# Converter_3V3-0V9_V2.net
KiCad netlist of a schematic drawn in Altium Designer
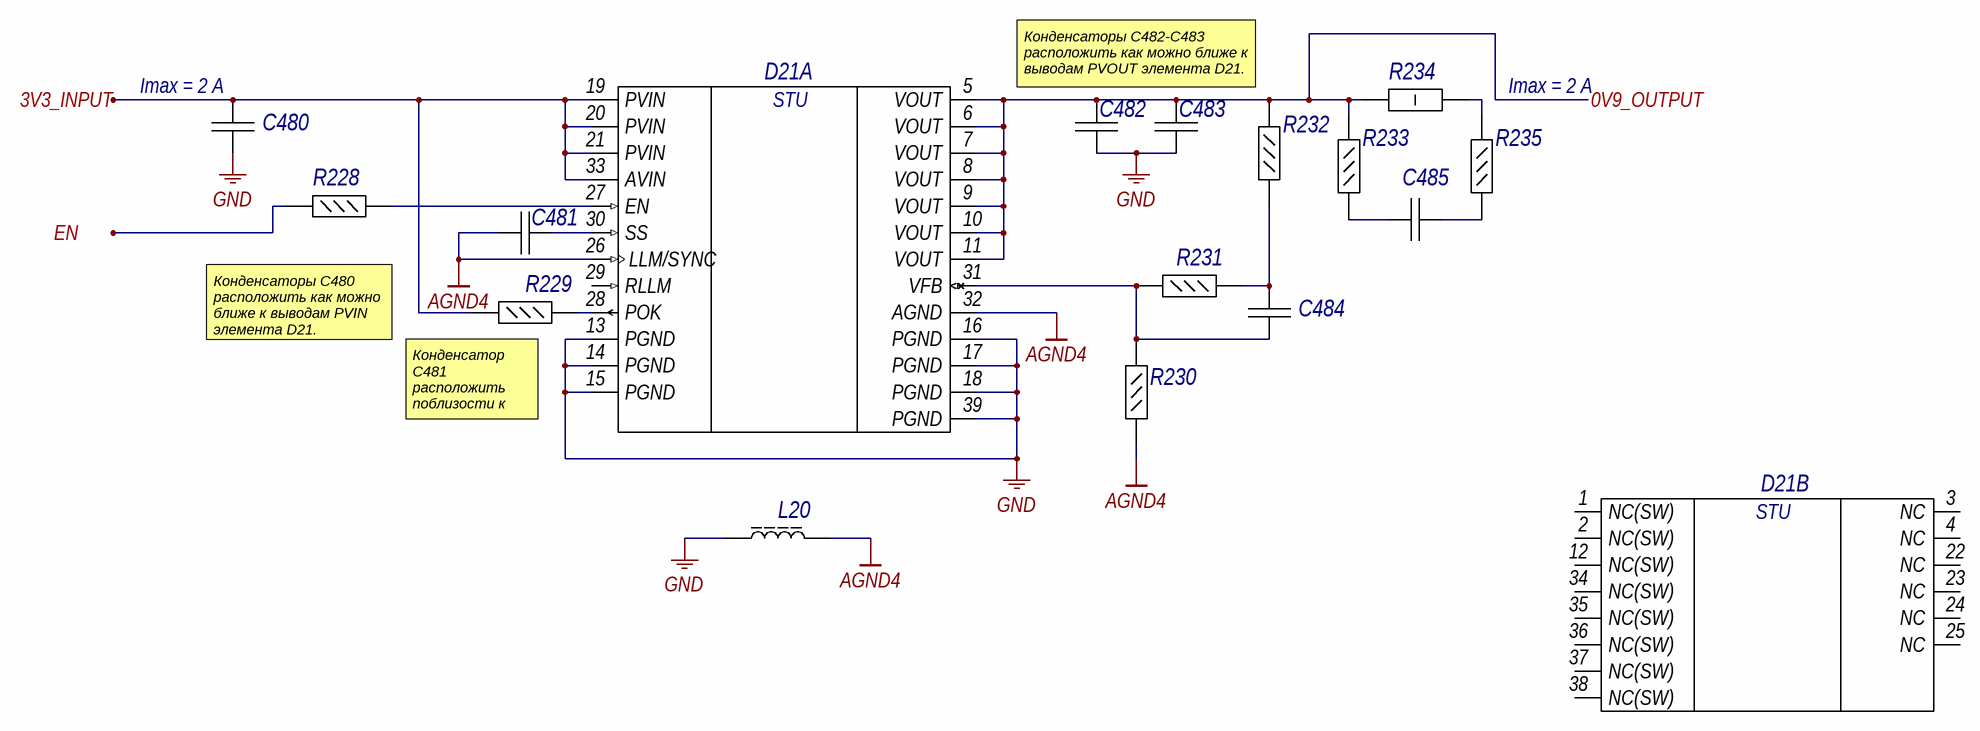
[diagram p0: Converter 3V3-0V9 V2.SchDoc]

(export (version "E")
  (design (tool "Eeschema 10.0.6"))
  (components
    (comp (ref "C480")
      (value "GRM31CR61E226KE15L")
      (footprint "CAPC3216X180X55ML20T25")
      (description "Chip Capacitor, 22 uF, +/- 10%, 25 V, -55 to 85 degC, 1206 (3216 Metric), RoHS, Tape and Reel")
      (fields (field (name "TOLERANCE") "10%"))
      (libsource (lib "MiniPC DB") (part "CAP_NP"))
    )
    (comp (ref "C481")
      (value "VJ0402Y153JXQPW1BC")
      (footprint "CAPC1005X55X23ML05T8")
      (description "Chip Capacitor, 15 nF, +/- 5%, 10 V, -55 to 125 degC, 0402 (1005 Metric), RoHS, Tape and Reel")
      (fields (field (name "TOLERANCE") "5%"))
      (libsource (lib "MiniPC DB") (part "CAP_NP"))
    )
    (comp (ref "C482")
      (value "C3216X5R1A476M160AB")
      (footprint "CAPC3216X180X20ML20")
      (description "Chip Capacitor, 47 uF, +/- 20%, 10 V, -55 to 85 degC, 1206 (3216 Metric), RoHS, Tape and Reel")
      (fields (field (name "TOLERANCE") "20%"))
      (libsource (lib "MiniPC DB") (part "CAP_NP"))
    )
    (comp (ref "C483")
      (value "C3216X5R1A476M160AB")
      (footprint "CAPC3216X180X20ML20")
      (description "Chip Capacitor, 47 uF, +/- 20%, 10 V, -55 to 85 degC, 1206 (3216 Metric), RoHS, Tape and Reel")
      (fields (field (name "TOLERANCE") "20%"))
      (libsource (lib "MiniPC DB") (part "CAP_NP"))
    )
    (comp (ref "C484")
      (value "ECJ-0EC1H150J")
      (footprint "CAPC1005X55X20ML5T10")
      (description "Chip Capacitor,15 pF, +/- 5%, 50 V, -55 to 125 degC, 0402 (1005 Metric), RoHS, Tape and Reel")
      (fields (field (name "TOLERANCE") "5%"))
      (libsource (lib "MiniPC DB") (part "CAP_NP"))
    )
    (comp (ref "C485")
      (value "CGB2A1X5R1E105K033BC")
      (footprint "CAPC1005X33X10LL5")
      (description "Chip Capacitor, 1 uF, +/- 10%, 25 V, -55 to 85 degC, 0402 (1005 Metric), RoHS, Tape and Reel")
      (fields (field (name "TOLERANCE") "10%"))
      (libsource (lib "MiniPC DB") (part "CAP_NP"))
    )
    (comp (ref "D21")
      (value "EN6337QI")
      (footprint "ALTR-QFN-38_A-190_D1-193_V")
      (libsource (lib "MiniPC DB") (part "EN6337QI"))
    )
    (comp (ref "L20")
      (value "742792609")
      (footprint "SMD-0603")
      (description "SMD EMI Suppression Ferrite Bead WE-CBF, Z = 30 Ohm")
      (libsource (lib "MiniPC DB") (part "Choke"))
    )
    (comp (ref "R228")
      (value "NRC04F49R9TRF")
      (footprint "RESC1005X35X25NL8T10")
      (description "Chip Resistor, 49.9 Ohm, +/- 1%, 0.06 W, -55 to 155 degC, 0402 (1005 Metric), RoHS, Tape and Reel")
      (fields (field (name "TOLERANCE") "1%"))
      (libsource (lib "") (part "RES-0.05_1"))
    )
    (comp (ref "R229")
      (value "ERJ-2RKF1003X")
      (footprint "RESC1005X40X25LL05T05")
      (description "Chip Resistor, 100 KOhm, +/- 1%, 100 mW, -55 to 155 degC, 0402 (1005 Metric), RoHS, Tape and Reel")
      (fields (field (name "TOLERANCE") "1%") (field (name "MANUFACTURER") "Basic Passives"))
      (libsource (lib "") (part "RES-0.05_1"))
    )
    (comp (ref "R230")
      (value "ERJ-2RKF1004X")
      (footprint "RESC1005X40X25LL05T05")
      (description "Chip Resistor, 1 MOhm, +/- 1%, 100 mW, -55 to 155 degC, 0402 (1005 Metric), RoHS, Tape and Reel")
      (fields (field (name "TOLERANCE") "1%") (field (name "MANUFACTURER") "Basic Passives"))
      (libsource (lib "") (part "RES-0.05_2"))
    )
    (comp (ref "R231")
      (value "ERJ-2RKF2003X")
      (footprint "RESC1005X40X25LL05T05")
      (description "Chip Resistor, 200 KOhm, +/- 1%, 100 mW, -55 to 155 degC, 0402 (1005 Metric), RoHS, Tape and Reel")
      (fields (field (name "TOLERANCE") "1%") (field (name "MANUFACTURER") "Basic Passives"))
      (libsource (lib "") (part "RES-0.05_1"))
    )
    (comp (ref "R232")
      (value "ERJ-2GE0R00X")
      (footprint "RESC1005X40X25LL05T05")
      (description "Chip Resistor, 0 mOhm, +/- 5%, 100 mW, -55 to 155 degC, 0402 (1005 Metric), RoHS, Tape and Reel")
      (fields (field (name "TOLERANCE") "5%") (field (name "MANUFACTURER") "Basic Passives"))
      (libsource (lib "MiniPC DB") (part "RES-0.05"))
    )
    (comp (ref "R233")
      (value "ERJ-2RKF1002X")
      (footprint "RESC1005X40X25LL05T05")
      (description "Chip Resistor, 10 KOhm, +/- 1%, 100 mW, -55 to 155 degC, 0402 (1005 Metric), RoHS, Tape and Reel")
      (fields (field (name "TOLERANCE") "1%") (field (name "MANUFACTURER") "Basic Passives"))
      (libsource (lib "") (part "RES-0.05_2"))
    )
    (comp (ref "R234")
      (value "WSLP12061L000FEA")
      (footprint "RESC3216X89X104LL25T25")
      (description "Chip Resistor, 0.001 Ohm, +/- 1%, 1 W, -65 to 170 degC, 1206 (3216 Metric), RoHS, Tape and Reel")
      (fields (field (name "TOLERANCE") "1%"))
      (libsource (lib "MiniPC DB") (part "RES-1"))
    )
    (comp (ref "R235")
      (value "ERJ-2RKF1002X")
      (footprint "RESC1005X40X25LL05T05")
      (description "Chip Resistor, 10 KOhm, +/- 1%, 100 mW, -55 to 155 degC, 0402 (1005 Metric), RoHS, Tape and Reel")
      (fields (field (name "TOLERANCE") "1%") (field (name "MANUFACTURER") "Basic Passives"))
      (libsource (lib "") (part "RES-0.05_2"))
    )
  )
  (nets
    (net (code "1") (name "/0V9_OUTPUT") (class "Default")
      (node (ref "C482") (pin "2") (pinfunction "2_2") (pintype "passive"))
      (node (ref "C483") (pin "2") (pinfunction "2_2") (pintype "passive"))
      (node (ref "D21") (pin "10") (pinfunction "VOUT_10") (pintype "power_in"))
      (node (ref "D21") (pin "11") (pinfunction "VOUT_11") (pintype "power_in"))
      (node (ref "D21") (pin "5") (pinfunction "VOUT_5") (pintype "power_in"))
      (node (ref "D21") (pin "6") (pinfunction "VOUT_6") (pintype "power_in"))
      (node (ref "D21") (pin "7") (pinfunction "VOUT_7") (pintype "power_in"))
      (node (ref "D21") (pin "8") (pinfunction "VOUT_8") (pintype "power_in"))
      (node (ref "D21") (pin "9") (pinfunction "VOUT_9") (pintype "power_in"))
      (node (ref "R232") (pin "1") (pinfunction "1_1") (pintype "passive"))
      (node (ref "R233") (pin "2") (pinfunction "2_2") (pintype "passive"))
      (node (ref "R234") (pin "2") (pinfunction "2_2") (pintype "passive"))
    )
    (net (code "2") (name "/3V3_INPUT") (class "Default")
      (node (ref "C480") (pin "2") (pinfunction "2_2") (pintype "passive"))
      (node (ref "D21") (pin "19") (pinfunction "PVIN_19") (pintype "power_in"))
      (node (ref "D21") (pin "20") (pinfunction "PVIN_20") (pintype "power_in"))
      (node (ref "D21") (pin "21") (pinfunction "PVIN_21") (pintype "power_in"))
      (node (ref "D21") (pin "33") (pinfunction "AVIN_33") (pintype "power_in"))
      (node (ref "R229") (pin "1") (pinfunction "1_1") (pintype "passive"))
    )
    (net (code "3") (name "/EN") (class "Default")
      (node (ref "R228") (pin "1") (pinfunction "1_1") (pintype "passive"))
    )
    (net (code "4") (name "AGND4") (class "Default")
      (node (ref "C481") (pin "1") (pinfunction "1_1") (pintype "passive"))
      (node (ref "D21") (pin "26") (pinfunction "LLM/SYNC_26") (pintype "input"))
      (node (ref "D21") (pin "32") (pinfunction "AGND_32") (pintype "power_in"))
      (node (ref "L20") (pin "2") (pinfunction "2_2") (pintype "passive"))
      (node (ref "R230") (pin "1") (pinfunction "1_1") (pintype "passive"))
    )
    (net (code "5") (name "GND") (class "Default")
      (node (ref "C480") (pin "1") (pinfunction "1_1") (pintype "passive"))
      (node (ref "C482") (pin "1") (pinfunction "1_1") (pintype "passive"))
      (node (ref "C483") (pin "1") (pinfunction "1_1") (pintype "passive"))
      (node (ref "D21") (pin "13") (pinfunction "PGND_13") (pintype "power_in"))
      (node (ref "D21") (pin "14") (pinfunction "PGND_14") (pintype "power_in"))
      (node (ref "D21") (pin "15") (pinfunction "PGND_15") (pintype "power_in"))
      (node (ref "D21") (pin "16") (pinfunction "PGND_16") (pintype "power_in"))
      (node (ref "D21") (pin "17") (pinfunction "PGND_17") (pintype "power_in"))
      (node (ref "D21") (pin "18") (pinfunction "PGND_18") (pintype "power_in"))
      (node (ref "D21") (pin "39") (pinfunction "PGND_39") (pintype "power_in"))
      (node (ref "L20") (pin "1") (pinfunction "1_1") (pintype "passive"))
    )
    (net (code "6") (name "Net-(C484-Pad2)") (class "Default")
      (node (ref "C484") (pin "2") (pinfunction "2_2") (pintype "passive"))
      (node (ref "R231") (pin "2") (pinfunction "2_2") (pintype "passive"))
      (node (ref "R232") (pin "2") (pinfunction "2_2") (pintype "passive"))
    )
    (net (code "7") (name "Net-(C485-Pad1)") (class "Default")
      (node (ref "C485") (pin "1") (pinfunction "1_1") (pintype "passive"))
      (node (ref "R233") (pin "1") (pinfunction "1_1") (pintype "passive"))
    )
    (net (code "8") (name "Net-(C485-Pad2)") (class "Default")
      (node (ref "C485") (pin "2") (pinfunction "2_2") (pintype "passive"))
      (node (ref "R235") (pin "1") (pinfunction "1_1") (pintype "passive"))
    )
    (net (code "9") (name "Net-(D21A-EN)") (class "Default")
      (node (ref "D21") (pin "27") (pinfunction "EN_27") (pintype "input"))
      (node (ref "R228") (pin "2") (pinfunction "2_2") (pintype "passive"))
    )
    (net (code "10") (name "Net-(D21A-POK)") (class "Default")
      (node (ref "D21") (pin "28") (pinfunction "POK_28") (pintype "open_collector"))
      (node (ref "R229") (pin "2") (pinfunction "2_2") (pintype "passive"))
    )
    (net (code "11") (name "Net-(D21A-SS)") (class "Default")
      (node (ref "C481") (pin "2") (pinfunction "2_2") (pintype "passive"))
      (node (ref "D21") (pin "30") (pinfunction "SS_30") (pintype "input"))
    )
    (net (code "12") (name "Net-(D21A-VFB)") (class "Default")
      (node (ref "C484") (pin "1") (pinfunction "1_1") (pintype "passive"))
      (node (ref "D21") (pin "31") (pinfunction "VFB_31") (pintype "input"))
      (node (ref "R230") (pin "2") (pinfunction "2_2") (pintype "passive"))
      (node (ref "R231") (pin "1") (pinfunction "1_1") (pintype "passive"))
    )
    (net (code "13") (name "Net-(R234-Pad1)") (class "Default")
      (node (ref "R234") (pin "1") (pinfunction "1_1") (pintype "passive"))
      (node (ref "R235") (pin "2") (pinfunction "2_2") (pintype "passive"))
    )
    (net (code "14") (name "unconnected-(D21A-RLLM-Pad29)") (class "Default")
      (node (ref "D21") (pin "29") (pinfunction "RLLM_29") (pintype "input"))
    )
    (net (code "15") (name "unconnected-(D21B-NC(SW)-Pad1)") (class "Default")
      (node (ref "D21") (pin "1") (pinfunction "NC(SW)_1") (pintype "passive"))
    )
    (net (code "16") (name "unconnected-(D21B-NC(SW)-Pad2)") (class "Default")
      (node (ref "D21") (pin "2") (pinfunction "NC(SW)_2") (pintype "passive"))
    )
    (net (code "17") (name "unconnected-(D21B-NC(SW)-Pad12)") (class "Default")
      (node (ref "D21") (pin "12") (pinfunction "NC(SW)_12") (pintype "passive"))
    )
    (net (code "18") (name "unconnected-(D21B-NC(SW)-Pad34)") (class "Default")
      (node (ref "D21") (pin "34") (pinfunction "NC(SW)_34") (pintype "passive"))
    )
    (net (code "19") (name "unconnected-(D21B-NC(SW)-Pad35)") (class "Default")
      (node (ref "D21") (pin "35") (pinfunction "NC(SW)_35") (pintype "passive"))
    )
    (net (code "20") (name "unconnected-(D21B-NC(SW)-Pad36)") (class "Default")
      (node (ref "D21") (pin "36") (pinfunction "NC(SW)_36") (pintype "passive"))
    )
    (net (code "21") (name "unconnected-(D21B-NC(SW)-Pad37)") (class "Default")
      (node (ref "D21") (pin "37") (pinfunction "NC(SW)_37") (pintype "passive"))
    )
    (net (code "22") (name "unconnected-(D21B-NC(SW)-Pad38)") (class "Default")
      (node (ref "D21") (pin "38") (pinfunction "NC(SW)_38") (pintype "passive"))
    )
    (net (code "23") (name "unconnected-(D21B-NC-Pad3)") (class "Default")
      (node (ref "D21") (pin "3") (pinfunction "NC_3") (pintype "passive"))
    )
    (net (code "24") (name "unconnected-(D21B-NC-Pad4)") (class "Default")
      (node (ref "D21") (pin "4") (pinfunction "NC_4") (pintype "passive"))
    )
    (net (code "25") (name "unconnected-(D21B-NC-Pad22)") (class "Default")
      (node (ref "D21") (pin "22") (pinfunction "NC_22") (pintype "passive"))
    )
    (net (code "26") (name "unconnected-(D21B-NC-Pad23)") (class "Default")
      (node (ref "D21") (pin "23") (pinfunction "NC_23") (pintype "passive"))
    )
    (net (code "27") (name "unconnected-(D21B-NC-Pad24)") (class "Default")
      (node (ref "D21") (pin "24") (pinfunction "NC_24") (pintype "passive"))
    )
    (net (code "28") (name "unconnected-(D21B-NC-Pad25)") (class "Default")
      (node (ref "D21") (pin "25") (pinfunction "NC_25") (pintype "passive"))
    )
  )
)
